# MinSys_atmega.net
KiCad netlist of a schematic drawn in EAGLE
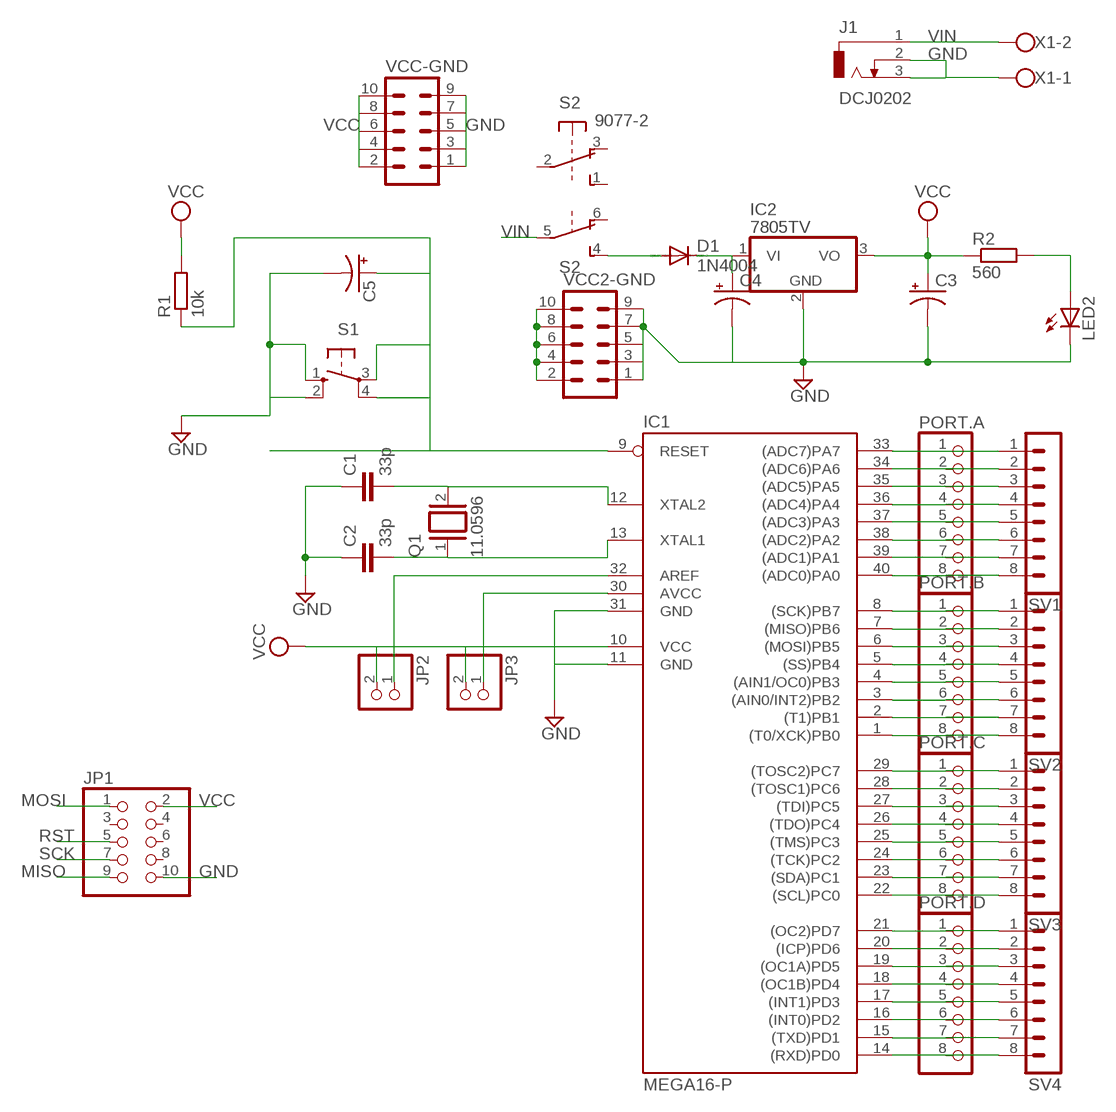
[diagram p0: schematic, sheet 1]

(export (version "E")
  (design (tool "Eeschema 10.0.6"))
  (components
    (comp (ref "C1")
      (value "33p")
      (footprint "eagle-import:C2.5-3")
      (libsource (lib "eagle-import") (part "C2,5-3"))
    )
    (comp (ref "C2")
      (value "33p")
      (footprint "eagle-import:C2.5-3")
      (libsource (lib "eagle-import") (part "C2,5-3"))
    )
    (comp (ref "C3")
      (value "CPOL-USE2,5-6E")
      (footprint "eagle-import:E2,5-6E")
      (libsource (lib "eagle-import") (part "CPOL-USE2,5-6E"))
    )
    (comp (ref "C4")
      (value "CPOL-USE2,5-6E")
      (footprint "eagle-import:E2,5-6E")
      (libsource (lib "eagle-import") (part "CPOL-USE2,5-6E"))
    )
    (comp (ref "C5")
      (value "CPOL-USE2.5-6")
      (footprint "eagle-import:E2,5-6")
      (libsource (lib "eagle-import") (part "CPOL-USE2.5-6"))
    )
    (comp (ref "D1")
      (value "1N4004")
      (footprint "eagle-import:DO41-10")
      (libsource (lib "eagle-import") (part "1N4004"))
    )
    (comp (ref "IC1")
      (value "MEGA16-P")
      (footprint "eagle-import:DIL40")
      (fields (field (name "MPN") "ATMEGA16-16PU"))
      (libsource (lib "eagle-import") (part "MEGA16-P"))
    )
    (comp (ref "IC2")
      (value "7805TV")
      (footprint "eagle-import:TO220V")
      (libsource (lib "eagle-import") (part "78TV05"))
    )
    (comp (ref "J1")
      (value "DCJ0202")
      (footprint "eagle-import:DCJ0202")
      (libsource (lib "eagle-import") (part "DCJ0202"))
    )
    (comp (ref "JP1")
      (value "PINHD-2X5")
      (footprint "eagle-import:2X05")
      (libsource (lib "eagle-import") (part "PINHD-2X5"))
    )
    (comp (ref "JP2")
      (value "PINHD-1X2")
      (footprint "eagle-import:1X02")
      (libsource (lib "eagle-import") (part "PINHD-1X2"))
    )
    (comp (ref "JP3")
      (value "PINHD-1X2")
      (footprint "eagle-import:1X02")
      (libsource (lib "eagle-import") (part "PINHD-1X2"))
    )
    (comp (ref "LED2")
      (value "LED3MM")
      (footprint "eagle-import:LED3MM")
      (libsource (lib "eagle-import") (part "LED3MM"))
    )
    (comp (ref "PORT.A")
      (value "PINHD-1X8")
      (footprint "eagle-import:1X08")
      (libsource (lib "eagle-import") (part "PINHD-1X8"))
    )
    (comp (ref "PORT.B")
      (value "PINHD-1X8")
      (footprint "eagle-import:1X08")
      (libsource (lib "eagle-import") (part "PINHD-1X8"))
    )
    (comp (ref "PORT.C")
      (value "PINHD-1X8")
      (footprint "eagle-import:1X08")
      (libsource (lib "eagle-import") (part "PINHD-1X8"))
    )
    (comp (ref "PORT.D")
      (value "PINHD-1X8")
      (footprint "eagle-import:1X08")
      (libsource (lib "eagle-import") (part "PINHD-1X8"))
    )
    (comp (ref "Q1")
      (value "11.0596")
      (footprint "eagle-import:QS")
      (libsource (lib "eagle-import") (part "XTAL/S"))
    )
    (comp (ref "R1")
      (value "10k")
      (footprint "eagle-import:0207_10")
      (libsource (lib "eagle-import") (part "R-EU_0207/10"))
    )
    (comp (ref "R2")
      (value "560")
      (footprint "eagle-import:0207_10")
      (libsource (lib "eagle-import") (part "resistor_R-EU_0207/10"))
    )
    (comp (ref "S1")
      (value "10-XX")
      (footprint "eagle-import:B3F-10XX")
      (fields (field (name "MPN") "B3F-1000"))
      (libsource (lib "eagle-import") (part "10-XX"))
    )
    (comp (ref "S2")
      (value "9077-2")
      (footprint "eagle-import:9077-2")
      (libsource (lib "eagle-import") (part "9077-2"))
    )
    (comp (ref "SV1")
      (value "MA08-1")
      (footprint "eagle-import:MA08-1")
      (libsource (lib "eagle-import") (part "MA08-1"))
    )
    (comp (ref "SV2")
      (value "MA08-1")
      (footprint "eagle-import:MA08-1")
      (libsource (lib "eagle-import") (part "MA08-1"))
    )
    (comp (ref "SV3")
      (value "MA08-1")
      (footprint "eagle-import:MA08-1")
      (libsource (lib "eagle-import") (part "MA08-1"))
    )
    (comp (ref "SV4")
      (value "MA08-1")
      (footprint "eagle-import:MA08-1")
      (libsource (lib "eagle-import") (part "MA08-1"))
    )
    (comp (ref "VCC-GND")
      (value "MA05-2")
      (footprint "eagle-import:MA05-2")
      (libsource (lib "eagle-import") (part "MA05-2"))
    )
    (comp (ref "VCC2-GND")
      (value "MA05-2")
      (footprint "eagle-import:MA05-2")
      (libsource (lib "eagle-import") (part "MA05-2"))
    )
    (comp (ref "X1")
      (value "W237-102")
      (footprint "eagle-import:W237-102")
      (fields (field (name "MPN") "237-102"))
      (libsource (lib "eagle-import") (part "W237-102"))
    )
  )
  (nets
    (net (code "1") (name "/MISO") (class "Default")
      (node (ref "IC1") (pin "7") (pinfunction "(MISO)PB6_7") (pintype "bidirectional"))
      (node (ref "JP1") (pin "9") (pinfunction "9_9") (pintype "passive"))
      (node (ref "PORT.B") (pin "2") (pinfunction "2_2") (pintype "passive"))
      (node (ref "SV2") (pin "2") (pinfunction "2_2") (pintype "passive"))
    )
    (net (code "2") (name "/MOSI") (class "Default")
      (node (ref "IC1") (pin "6") (pinfunction "(MOSI)PB5_6") (pintype "bidirectional"))
      (node (ref "JP1") (pin "1") (pinfunction "1_1") (pintype "passive"))
      (node (ref "PORT.B") (pin "3") (pinfunction "3_3") (pintype "passive"))
      (node (ref "SV2") (pin "3") (pinfunction "3_3") (pintype "passive"))
    )
    (net (code "3") (name "/RST") (class "Default")
      (node (ref "C5") (pin "+") (pinfunction "+_+") (pintype "passive"))
      (node (ref "IC1") (pin "9") (pinfunction "RESET_9") (pintype "input"))
      (node (ref "JP1") (pin "5") (pinfunction "5_5") (pintype "passive"))
      (node (ref "R1") (pin "1") (pinfunction "1_1") (pintype "passive"))
      (node (ref "S1") (pin "3") (pinfunction "P_3") (pintype "passive"))
      (node (ref "S1") (pin "4") (pinfunction "P1_4") (pintype "passive"))
    )
    (net (code "4") (name "/SCK") (class "Default")
      (node (ref "IC1") (pin "8") (pinfunction "(SCK)PB7_8") (pintype "bidirectional"))
      (node (ref "JP1") (pin "7") (pinfunction "7_7") (pintype "passive"))
      (node (ref "PORT.B") (pin "1") (pinfunction "1_1") (pintype "passive"))
      (node (ref "SV2") (pin "1") (pinfunction "1_1") (pintype "passive"))
    )
    (net (code "5") (name "/VIN") (class "Default")
      (node (ref "J1") (pin "1") (pinfunction "1_1") (pintype "passive"))
      (node (ref "S2") (pin "5") (pinfunction "P_5") (pintype "passive"))
      (node (ref "X1") (pin "2") (pinfunction "KL_2") (pintype "passive"))
    )
    (net (code "6") (name "GND") (class "Default")
      (node (ref "C1") (pin "1") (pinfunction "1_1") (pintype "passive"))
      (node (ref "C2") (pin "1") (pinfunction "1_1") (pintype "passive"))
      (node (ref "C3") (pin "-") (pinfunction "-_-") (pintype "passive"))
      (node (ref "C4") (pin "-") (pinfunction "-_-") (pintype "passive"))
      (node (ref "C5") (pin "-") (pinfunction "-_-") (pintype "passive"))
      (node (ref "IC1") (pin "11") (pinfunction "GND_11") (pintype "power_in"))
      (node (ref "IC1") (pin "31") (pinfunction "GND_31") (pintype "power_in"))
      (node (ref "IC2") (pin "2") (pinfunction "GND_2") (pintype "passive"))
      (node (ref "J1") (pin "2") (pinfunction "2_2") (pintype "passive"))
      (node (ref "J1") (pin "3") (pinfunction "3_3") (pintype "passive"))
      (node (ref "JP1") (pin "10") (pinfunction "10_10") (pintype "passive"))
      (node (ref "LED2") (pin "K") (pinfunction "C_K") (pintype "passive"))
      (node (ref "S1") (pin "1") (pinfunction "S_1") (pintype "passive"))
      (node (ref "S1") (pin "2") (pinfunction "S1_2") (pintype "passive"))
      (node (ref "VCC-GND") (pin "1") (pinfunction "1_1") (pintype "passive"))
      (node (ref "VCC-GND") (pin "3") (pinfunction "3_3") (pintype "passive"))
      (node (ref "VCC-GND") (pin "5") (pinfunction "5_5") (pintype "passive"))
      (node (ref "VCC-GND") (pin "7") (pinfunction "7_7") (pintype "passive"))
      (node (ref "VCC-GND") (pin "9") (pinfunction "9_9") (pintype "passive"))
      (node (ref "VCC2-GND") (pin "1") (pinfunction "1_1") (pintype "passive"))
      (node (ref "VCC2-GND") (pin "3") (pinfunction "3_3") (pintype "passive"))
      (node (ref "VCC2-GND") (pin "5") (pinfunction "5_5") (pintype "passive"))
      (node (ref "VCC2-GND") (pin "7") (pinfunction "7_7") (pintype "passive"))
      (node (ref "VCC2-GND") (pin "9") (pinfunction "9_9") (pintype "passive"))
      (node (ref "X1") (pin "1") (pinfunction "KL_1") (pintype "passive"))
    )
    (net (code "7") (name "Net-(IC1-(ADC0)PA0)") (class "Default")
      (node (ref "IC1") (pin "40") (pinfunction "(ADC0)PA0_40") (pintype "bidirectional"))
      (node (ref "PORT.A") (pin "8") (pinfunction "8_8") (pintype "passive"))
      (node (ref "SV1") (pin "8") (pinfunction "8_8") (pintype "passive"))
    )
    (net (code "8") (name "Net-(IC1-(ADC1)PA1)") (class "Default")
      (node (ref "IC1") (pin "39") (pinfunction "(ADC1)PA1_39") (pintype "bidirectional"))
      (node (ref "PORT.A") (pin "7") (pinfunction "7_7") (pintype "passive"))
      (node (ref "SV1") (pin "7") (pinfunction "7_7") (pintype "passive"))
    )
    (net (code "9") (name "Net-(IC1-(ADC2)PA2)") (class "Default")
      (node (ref "IC1") (pin "38") (pinfunction "(ADC2)PA2_38") (pintype "bidirectional"))
      (node (ref "PORT.A") (pin "6") (pinfunction "6_6") (pintype "passive"))
      (node (ref "SV1") (pin "6") (pinfunction "6_6") (pintype "passive"))
    )
    (net (code "10") (name "Net-(IC1-(ADC3)PA3)") (class "Default")
      (node (ref "IC1") (pin "37") (pinfunction "(ADC3)PA3_37") (pintype "bidirectional"))
      (node (ref "PORT.A") (pin "5") (pinfunction "5_5") (pintype "passive"))
      (node (ref "SV1") (pin "5") (pinfunction "5_5") (pintype "passive"))
    )
    (net (code "11") (name "Net-(IC1-(ADC4)PA4)") (class "Default")
      (node (ref "IC1") (pin "36") (pinfunction "(ADC4)PA4_36") (pintype "bidirectional"))
      (node (ref "PORT.A") (pin "4") (pinfunction "4_4") (pintype "passive"))
      (node (ref "SV1") (pin "4") (pinfunction "4_4") (pintype "passive"))
    )
    (net (code "12") (name "Net-(IC1-(ADC5)PA5)") (class "Default")
      (node (ref "IC1") (pin "35") (pinfunction "(ADC5)PA5_35") (pintype "bidirectional"))
      (node (ref "PORT.A") (pin "3") (pinfunction "3_3") (pintype "passive"))
      (node (ref "SV1") (pin "3") (pinfunction "3_3") (pintype "passive"))
    )
    (net (code "13") (name "Net-(IC1-(ADC6)PA6)") (class "Default")
      (node (ref "IC1") (pin "34") (pinfunction "(ADC6)PA6_34") (pintype "bidirectional"))
      (node (ref "PORT.A") (pin "2") (pinfunction "2_2") (pintype "passive"))
      (node (ref "SV1") (pin "2") (pinfunction "2_2") (pintype "passive"))
    )
    (net (code "14") (name "Net-(IC1-(ADC7)PA7)") (class "Default")
      (node (ref "IC1") (pin "33") (pinfunction "(ADC7)PA7_33") (pintype "bidirectional"))
      (node (ref "PORT.A") (pin "1") (pinfunction "1_1") (pintype "passive"))
      (node (ref "SV1") (pin "1") (pinfunction "1_1") (pintype "passive"))
    )
    (net (code "15") (name "Net-(IC1-(AIN0{slash}INT2)PB2)") (class "Default")
      (node (ref "IC1") (pin "3") (pinfunction "(AIN0/INT2)PB2_3") (pintype "bidirectional"))
      (node (ref "PORT.B") (pin "6") (pinfunction "6_6") (pintype "passive"))
      (node (ref "SV2") (pin "6") (pinfunction "6_6") (pintype "passive"))
    )
    (net (code "16") (name "Net-(IC1-(AIN1{slash}OC0)PB3)") (class "Default")
      (node (ref "IC1") (pin "4") (pinfunction "(AIN1/OC0)PB3_4") (pintype "bidirectional"))
      (node (ref "PORT.B") (pin "5") (pinfunction "5_5") (pintype "passive"))
      (node (ref "SV2") (pin "5") (pinfunction "5_5") (pintype "passive"))
    )
    (net (code "17") (name "Net-(IC1-(ICP)PD6)") (class "Default")
      (node (ref "IC1") (pin "20") (pinfunction "(ICP)PD6_20") (pintype "bidirectional"))
      (node (ref "PORT.D") (pin "2") (pinfunction "2_2") (pintype "passive"))
      (node (ref "SV4") (pin "2") (pinfunction "2_2") (pintype "passive"))
    )
    (net (code "18") (name "Net-(IC1-(INT0)PD2)") (class "Default")
      (node (ref "IC1") (pin "16") (pinfunction "(INT0)PD2_16") (pintype "bidirectional"))
      (node (ref "PORT.D") (pin "6") (pinfunction "6_6") (pintype "passive"))
      (node (ref "SV4") (pin "6") (pinfunction "6_6") (pintype "passive"))
    )
    (net (code "19") (name "Net-(IC1-(INT1)PD3)") (class "Default")
      (node (ref "IC1") (pin "17") (pinfunction "(INT1)PD3_17") (pintype "bidirectional"))
      (node (ref "PORT.D") (pin "5") (pinfunction "5_5") (pintype "passive"))
      (node (ref "SV4") (pin "5") (pinfunction "5_5") (pintype "passive"))
    )
    (net (code "20") (name "Net-(IC1-(OC1A)PD5)") (class "Default")
      (node (ref "IC1") (pin "19") (pinfunction "(OC1A)PD5_19") (pintype "bidirectional"))
      (node (ref "PORT.D") (pin "3") (pinfunction "3_3") (pintype "passive"))
      (node (ref "SV4") (pin "3") (pinfunction "3_3") (pintype "passive"))
    )
    (net (code "21") (name "Net-(IC1-(OC1B)PD4)") (class "Default")
      (node (ref "IC1") (pin "18") (pinfunction "(OC1B)PD4_18") (pintype "bidirectional"))
      (node (ref "PORT.D") (pin "4") (pinfunction "4_4") (pintype "passive"))
      (node (ref "SV4") (pin "4") (pinfunction "4_4") (pintype "passive"))
    )
    (net (code "22") (name "Net-(IC1-(OC2)PD7)") (class "Default")
      (node (ref "IC1") (pin "21") (pinfunction "(OC2)PD7_21") (pintype "bidirectional"))
      (node (ref "PORT.D") (pin "1") (pinfunction "1_1") (pintype "passive"))
      (node (ref "SV4") (pin "1") (pinfunction "1_1") (pintype "passive"))
    )
    (net (code "23") (name "Net-(IC1-(RXD)PD0)") (class "Default")
      (node (ref "IC1") (pin "14") (pinfunction "(RXD)PD0_14") (pintype "bidirectional"))
      (node (ref "PORT.D") (pin "8") (pinfunction "8_8") (pintype "passive"))
      (node (ref "SV4") (pin "8") (pinfunction "8_8") (pintype "passive"))
    )
    (net (code "24") (name "Net-(IC1-(SCL)PC0)") (class "Default")
      (node (ref "IC1") (pin "22") (pinfunction "(SCL)PC0_22") (pintype "bidirectional"))
      (node (ref "PORT.C") (pin "8") (pinfunction "8_8") (pintype "passive"))
      (node (ref "SV3") (pin "8") (pinfunction "8_8") (pintype "passive"))
    )
    (net (code "25") (name "Net-(IC1-(SDA)PC1)") (class "Default")
      (node (ref "IC1") (pin "23") (pinfunction "(SDA)PC1_23") (pintype "bidirectional"))
      (node (ref "PORT.C") (pin "7") (pinfunction "7_7") (pintype "passive"))
      (node (ref "SV3") (pin "7") (pinfunction "7_7") (pintype "passive"))
    )
    (net (code "26") (name "Net-(IC1-(SS)PB4)") (class "Default")
      (node (ref "IC1") (pin "5") (pinfunction "(SS)PB4_5") (pintype "bidirectional"))
      (node (ref "PORT.B") (pin "4") (pinfunction "4_4") (pintype "passive"))
      (node (ref "SV2") (pin "4") (pinfunction "4_4") (pintype "passive"))
    )
    (net (code "27") (name "Net-(IC1-(T0{slash}XCK)PB0)") (class "Default")
      (node (ref "IC1") (pin "1") (pinfunction "(T0/XCK)PB0_1") (pintype "bidirectional"))
      (node (ref "PORT.B") (pin "8") (pinfunction "8_8") (pintype "passive"))
      (node (ref "SV2") (pin "8") (pinfunction "8_8") (pintype "passive"))
    )
    (net (code "28") (name "Net-(IC1-(T1)PB1)") (class "Default")
      (node (ref "IC1") (pin "2") (pinfunction "(T1)PB1_2") (pintype "bidirectional"))
      (node (ref "PORT.B") (pin "7") (pinfunction "7_7") (pintype "passive"))
      (node (ref "SV2") (pin "7") (pinfunction "7_7") (pintype "passive"))
    )
    (net (code "29") (name "Net-(IC1-(TCK)PC2)") (class "Default")
      (node (ref "IC1") (pin "24") (pinfunction "(TCK)PC2_24") (pintype "bidirectional"))
      (node (ref "PORT.C") (pin "6") (pinfunction "6_6") (pintype "passive"))
      (node (ref "SV3") (pin "6") (pinfunction "6_6") (pintype "passive"))
    )
    (net (code "30") (name "Net-(IC1-(TDI)PC5)") (class "Default")
      (node (ref "IC1") (pin "27") (pinfunction "(TDI)PC5_27") (pintype "bidirectional"))
      (node (ref "PORT.C") (pin "3") (pinfunction "3_3") (pintype "passive"))
      (node (ref "SV3") (pin "3") (pinfunction "3_3") (pintype "passive"))
    )
    (net (code "31") (name "Net-(IC1-(TDO)PC4)") (class "Default")
      (node (ref "IC1") (pin "26") (pinfunction "(TDO)PC4_26") (pintype "bidirectional"))
      (node (ref "PORT.C") (pin "4") (pinfunction "4_4") (pintype "passive"))
      (node (ref "SV3") (pin "4") (pinfunction "4_4") (pintype "passive"))
    )
    (net (code "32") (name "Net-(IC1-(TMS)PC3)") (class "Default")
      (node (ref "IC1") (pin "25") (pinfunction "(TMS)PC3_25") (pintype "bidirectional"))
      (node (ref "PORT.C") (pin "5") (pinfunction "5_5") (pintype "passive"))
      (node (ref "SV3") (pin "5") (pinfunction "5_5") (pintype "passive"))
    )
    (net (code "33") (name "Net-(IC1-(TOSC1)PC6)") (class "Default")
      (node (ref "IC1") (pin "28") (pinfunction "(TOSC1)PC6_28") (pintype "bidirectional"))
      (node (ref "PORT.C") (pin "2") (pinfunction "2_2") (pintype "passive"))
      (node (ref "SV3") (pin "2") (pinfunction "2_2") (pintype "passive"))
    )
    (net (code "34") (name "Net-(IC1-(TOSC2)PC7)") (class "Default")
      (node (ref "IC1") (pin "29") (pinfunction "(TOSC2)PC7_29") (pintype "bidirectional"))
      (node (ref "PORT.C") (pin "1") (pinfunction "1_1") (pintype "passive"))
      (node (ref "SV3") (pin "1") (pinfunction "1_1") (pintype "passive"))
    )
    (net (code "35") (name "Net-(IC1-(TXD)PD1)") (class "Default")
      (node (ref "IC1") (pin "15") (pinfunction "(TXD)PD1_15") (pintype "bidirectional"))
      (node (ref "PORT.D") (pin "7") (pinfunction "7_7") (pintype "passive"))
      (node (ref "SV4") (pin "7") (pinfunction "7_7") (pintype "passive"))
    )
    (net (code "36") (name "Net-(IC1-AREF)") (class "Default")
      (node (ref "IC1") (pin "32") (pinfunction "AREF_32") (pintype "passive"))
      (node (ref "JP2") (pin "1") (pinfunction "1_1") (pintype "passive"))
    )
    (net (code "37") (name "Net-(IC1-AVCC)") (class "Default")
      (node (ref "IC1") (pin "30") (pinfunction "AVCC_30") (pintype "power_in"))
      (node (ref "JP3") (pin "1") (pinfunction "1_1") (pintype "passive"))
    )
    (net (code "38") (name "Net-(IC1-XTAL1)") (class "Default")
      (node (ref "C2") (pin "2") (pinfunction "2_2") (pintype "passive"))
      (node (ref "IC1") (pin "13") (pinfunction "XTAL1_13") (pintype "bidirectional"))
      (node (ref "Q1") (pin "1") (pinfunction "1_1") (pintype "passive"))
    )
    (net (code "39") (name "Net-(IC1-XTAL2)") (class "Default")
      (node (ref "C1") (pin "2") (pinfunction "2_2") (pintype "passive"))
      (node (ref "IC1") (pin "12") (pinfunction "XTAL2_12") (pintype "bidirectional"))
      (node (ref "Q1") (pin "2") (pinfunction "2_2") (pintype "passive"))
    )
    (net (code "40") (name "Net-(IC2-VI)") (class "Default")
      (node (ref "C4") (pin "+") (pinfunction "+_+") (pintype "passive"))
      (node (ref "D1") (pin "C") (pinfunction "C_C") (pintype "passive"))
      (node (ref "IC2") (pin "1") (pinfunction "VI_1") (pintype "input"))
    )
    (net (code "41") (name "Net-(LED2-PadA)") (class "Default")
      (node (ref "LED2") (pin "A") (pinfunction "A_A") (pintype "passive"))
      (node (ref "R2") (pin "2") (pinfunction "2_2") (pintype "passive"))
    )
    (net (code "42") (name "Net-(S2B-S)") (class "Default")
      (node (ref "D1") (pin "A") (pinfunction "A_A") (pintype "passive"))
      (node (ref "S2") (pin "4") (pinfunction "S_4") (pintype "passive"))
    )
    (net (code "43") (name "VCC") (class "Default")
      (node (ref "C3") (pin "+") (pinfunction "+_+") (pintype "passive"))
      (node (ref "IC1") (pin "10") (pinfunction "VCC_10") (pintype "power_in"))
      (node (ref "IC2") (pin "3") (pinfunction "VO_3") (pintype "passive"))
      (node (ref "JP1") (pin "2") (pinfunction "2_2") (pintype "passive"))
      (node (ref "JP2") (pin "2") (pinfunction "2_2") (pintype "passive"))
      (node (ref "JP3") (pin "2") (pinfunction "2_2") (pintype "passive"))
      (node (ref "R1") (pin "2") (pinfunction "2_2") (pintype "passive"))
      (node (ref "R2") (pin "1") (pinfunction "1_1") (pintype "passive"))
      (node (ref "VCC-GND") (pin "10") (pinfunction "10_10") (pintype "passive"))
      (node (ref "VCC-GND") (pin "2") (pinfunction "2_2") (pintype "passive"))
      (node (ref "VCC-GND") (pin "4") (pinfunction "4_4") (pintype "passive"))
      (node (ref "VCC-GND") (pin "6") (pinfunction "6_6") (pintype "passive"))
      (node (ref "VCC-GND") (pin "8") (pinfunction "8_8") (pintype "passive"))
      (node (ref "VCC2-GND") (pin "10") (pinfunction "10_10") (pintype "passive"))
      (node (ref "VCC2-GND") (pin "2") (pinfunction "2_2") (pintype "passive"))
      (node (ref "VCC2-GND") (pin "4") (pinfunction "4_4") (pintype "passive"))
      (node (ref "VCC2-GND") (pin "6") (pinfunction "6_6") (pintype "passive"))
      (node (ref "VCC2-GND") (pin "8") (pinfunction "8_8") (pintype "passive"))
    )
    (net (code "44") (name "unconnected-(JP1-Pad3)") (class "Default")
      (node (ref "JP1") (pin "3") (pinfunction "3_3") (pintype "passive"))
    )
    (net (code "45") (name "unconnected-(JP1-Pad4)") (class "Default")
      (node (ref "JP1") (pin "4") (pinfunction "4_4") (pintype "passive"))
    )
    (net (code "46") (name "unconnected-(JP1-Pad6)") (class "Default")
      (node (ref "JP1") (pin "6") (pinfunction "6_6") (pintype "passive"))
    )
    (net (code "47") (name "unconnected-(JP1-Pad8)") (class "Default")
      (node (ref "JP1") (pin "8") (pinfunction "8_8") (pintype "passive"))
    )
    (net (code "48") (name "unconnected-(S2A-O-Pad3)") (class "Default")
      (node (ref "S2") (pin "3") (pinfunction "O_3") (pintype "passive"))
    )
    (net (code "49") (name "unconnected-(S2A-P-Pad2)") (class "Default")
      (node (ref "S2") (pin "2") (pinfunction "P_2") (pintype "passive"))
    )
    (net (code "50") (name "unconnected-(S2A-S-Pad1)") (class "Default")
      (node (ref "S2") (pin "1") (pinfunction "S_1") (pintype "passive"))
    )
    (net (code "51") (name "unconnected-(S2B-O-Pad6)") (class "Default")
      (node (ref "S2") (pin "6") (pinfunction "O_6") (pintype "passive"))
    )
  )
)
